# 6502v2.net
KiCad netlist of a schematic drawn in EasyEDA
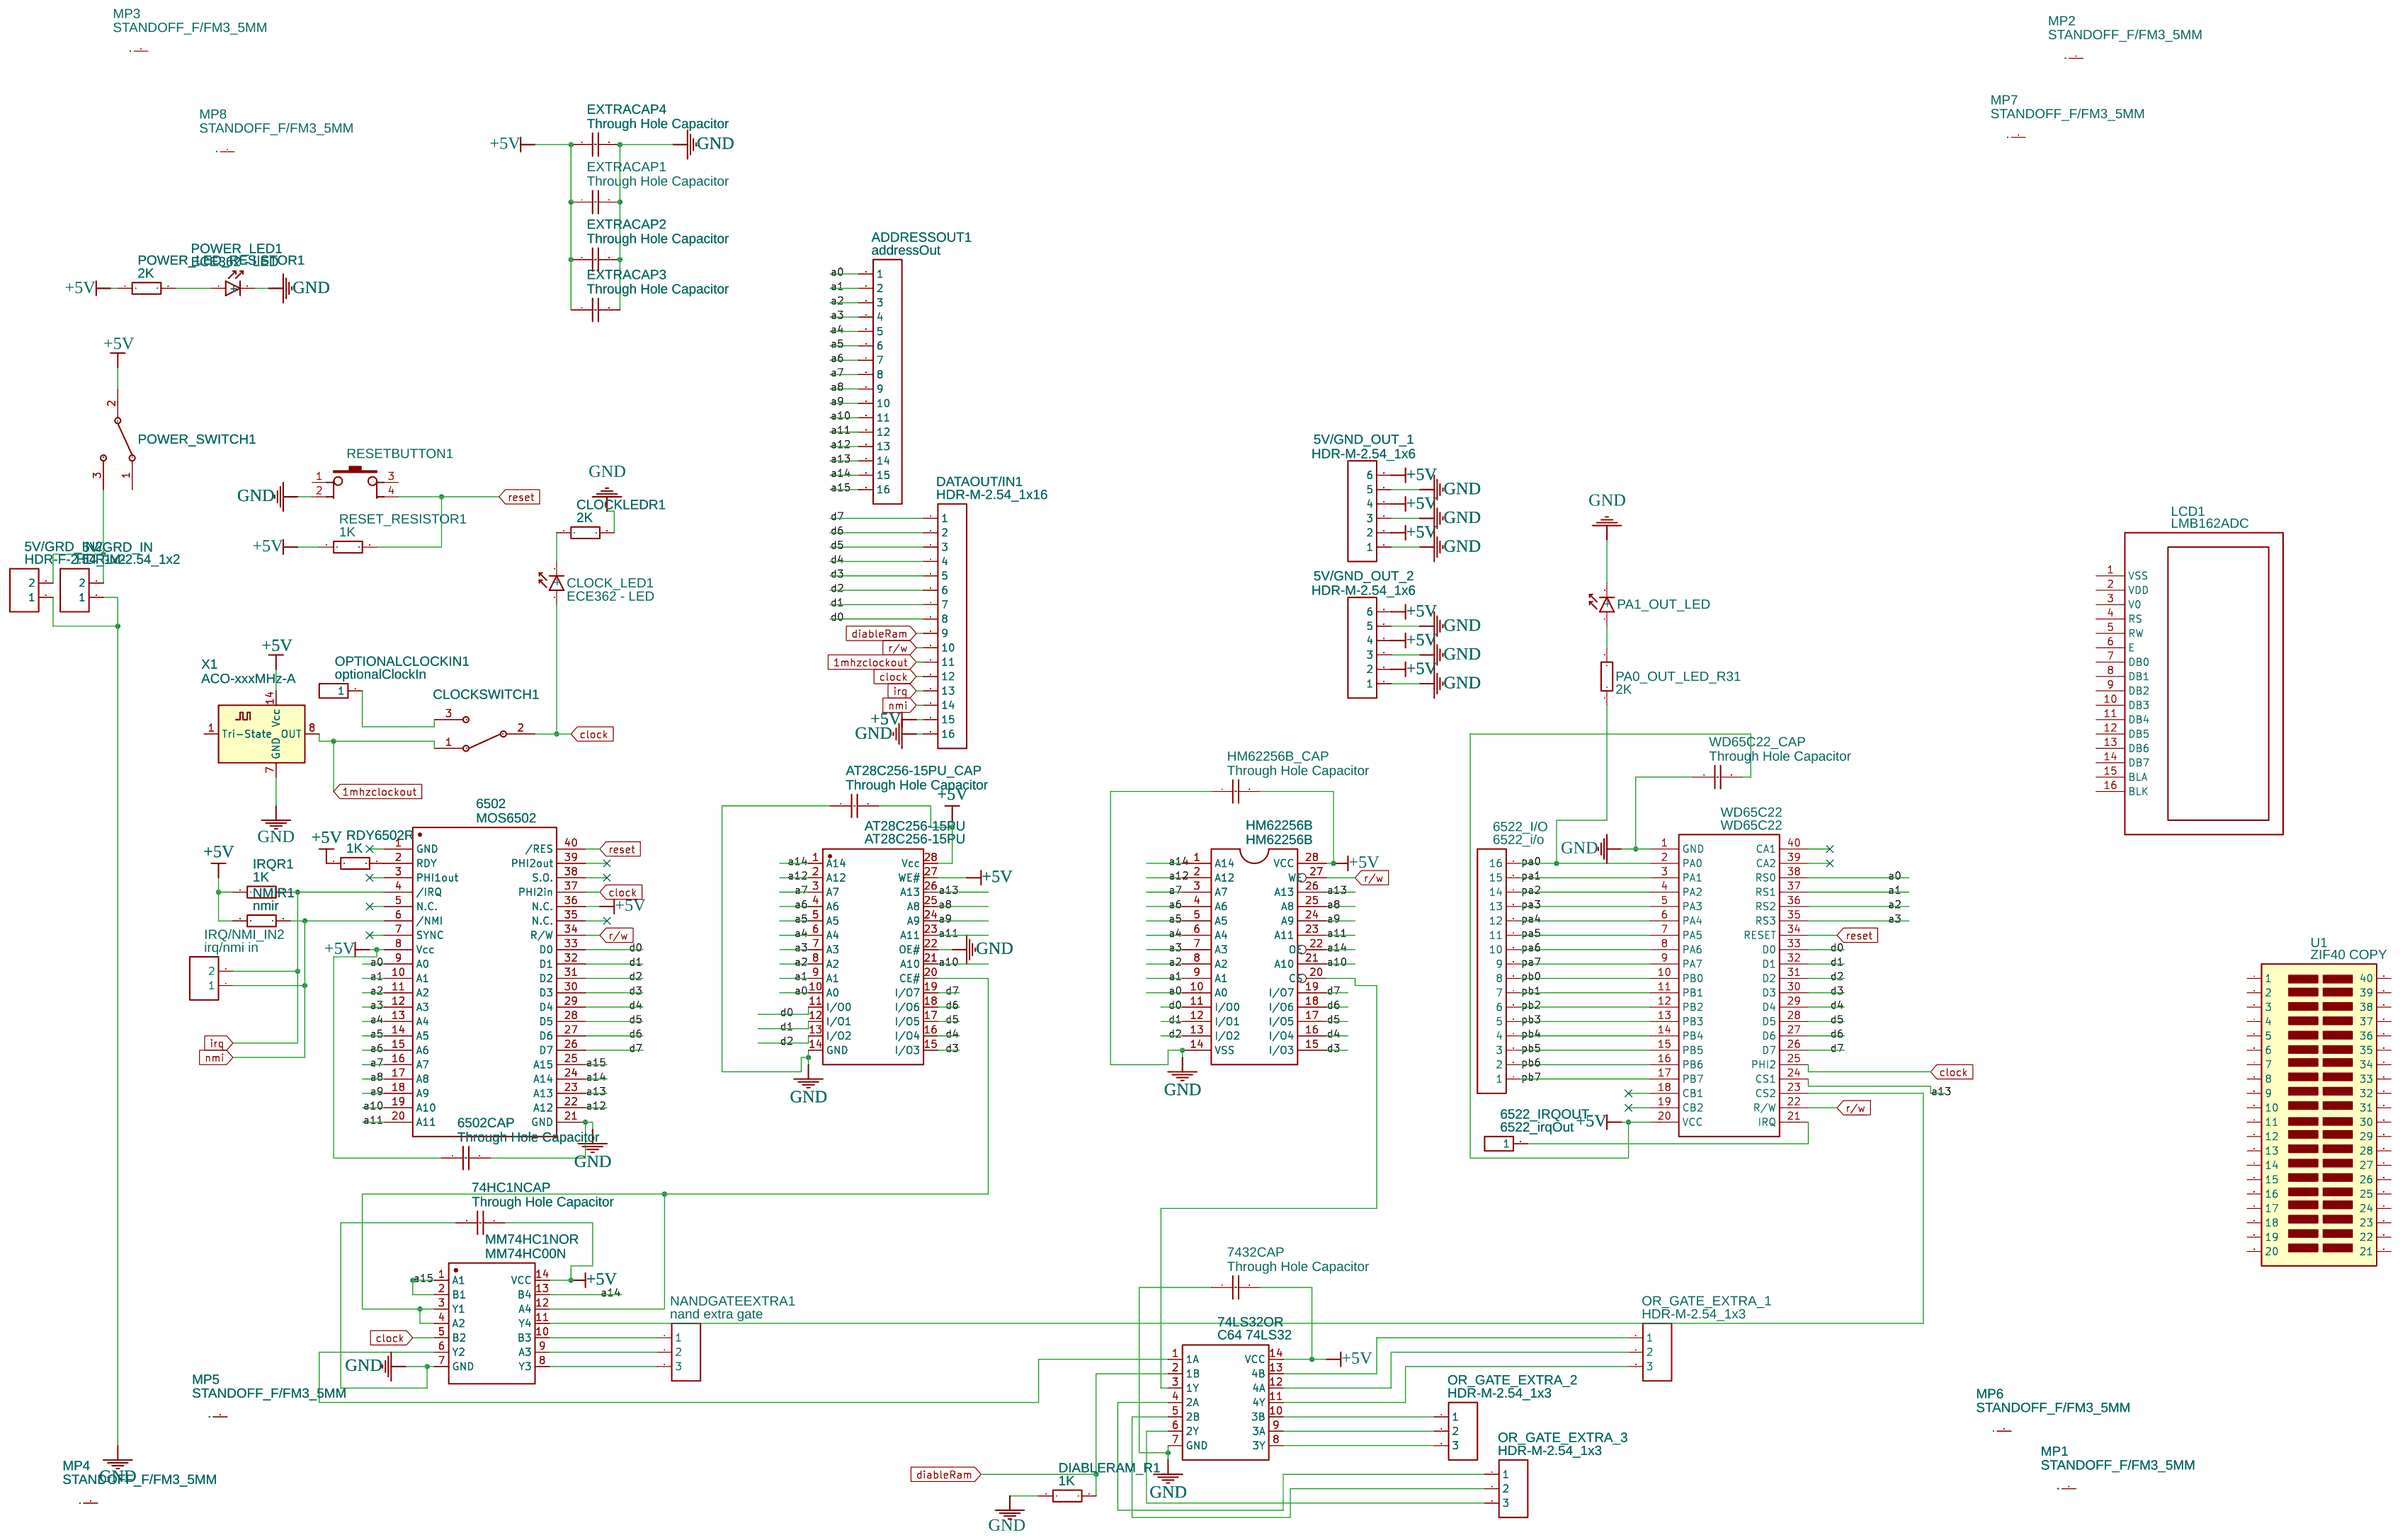
[diagram p0: schematic sheet]

(export (version "E")
  (design (tool "Eeschema 10.0.6"))
  (components
    (comp (ref "5V/GND_OUT_1")
      (value "HDR-M-2.54_1x6")
      (fields (field (name "BOM_Supplier Part") "C190819"))
      (libsource (lib "") (part "HDR-M-2.54_1x6"))
    )
    (comp (ref "5V/GND_OUT_2")
      (value "HDR-M-2.54_1x6")
      (fields (field (name "BOM_Supplier Part") "C190819"))
      (libsource (lib "") (part "HDR-M-2.54_1x6"))
    )
    (comp (ref "5V/GRD_IN")
      (value "HDR-M-2.54_1x2")
      (fields (field (name "BOM_Supplier Part") "C124375"))
      (libsource (lib "") (part "HDR-M-2.54_1x2"))
    )
    (comp (ref "5V/GRD_IN2")
      (value "HDR-F-2.54_1x2")
      (fields (field (name "BOM_Supplier Part") "C49661"))
      (libsource (lib "") (part "HDR-F-2.54_1x2_1"))
    )
    (comp (ref "74HC1NCAP")
      (value "Through Hole Capacitor")
      (fields (field (name "BOM_Manufacturer Part") "TAP106K016SCS"))
      (libsource (lib "") (part "Through Hole Capacitor_2"))
    )
    (comp (ref "74LS32OR") (value "C64 74LS32") (libsource (lib "") (part "C64 74LS32")))
    (comp (ref "6502") (value "MOS6502") (libsource (lib "") (part "MOS6502")))
    (comp (ref "6502CAP")
      (value "Through Hole Capacitor")
      (fields (field (name "BOM_Manufacturer Part") "TAP106K016SCS"))
      (libsource (lib "") (part "Through Hole Capacitor_3"))
    )
    (comp (ref "6522_I/O") (value "6522_i/o") (libsource (lib "") (part "HDR-M-2.54_1x16_1")))
    (comp (ref "6522_IRQOUT")
      (value "6522_irqOut")
      (fields (field (name "BOM_Supplier Part") "C81276"))
      (libsource (lib "") (part "HDR-M-2.54_1x1"))
    )
    (comp (ref "7432CAP")
      (value "Through Hole Capacitor")
      (fields (field (name "BOM_Manufacturer Part") "TAP106K016SCS"))
      (libsource (lib "") (part "Through Hole Capacitor_4"))
    )
    (comp (ref "ADDRESSOUT1") (value "addressOut") (libsource (lib "") (part "HDR-M-2.54_1x16")))
    (comp (ref "AT28C256-15PU")
      (value "AT28C256-15PU")
      (fields (field (name "BOM_Supplier Part") "C1348752"))
      (libsource (lib "") (part "AT28C256-15PU"))
    )
    (comp (ref "AT28C256-15PU_CAP")
      (value "Through Hole Capacitor")
      (fields (field (name "BOM_Manufacturer Part") "TAP106K016SCS"))
      (libsource (lib "") (part "Through Hole Capacitor_5"))
    )
    (comp (ref "CLOCKLEDR1")
      (value "2K")
      (fields
        (field (name "BOM_Manufacturer Part") "EWWR0006J10K0T9")
        (field (name "BOM_Supplier Part") "C348946")
      )
      (libsource (lib "") (part "GENERIC THROUGH HOLE RESISTOR 2_3"))
    )
    (comp (ref "CLOCKSWITCH1")
      (value "Slide Switches_SPDT(Single Pole Double Throw)")
      (libsource (lib "") (part "Slide Switches_SPDT(Single Pole Double Throw)"))
    )
    (comp (ref "CLOCK_LED1") (value "ECE362 - LED") (libsource (lib "") (part "ECE362 - LED")))
    (comp (ref "DATAOUT/IN1") (value "HDR-M-2.54_1x16") (libsource (lib "") (part "HDR-M-2.54_1x16_2")))
    (comp (ref "DIABLERAM_R1")
      (value "1K")
      (fields
        (field (name "BOM_Manufacturer Part") "EWWR0006J10K0T9")
        (field (name "BOM_Supplier Part") "C348946")
      )
      (libsource (lib "") (part "GENERIC THROUGH HOLE RESISTOR 2_1"))
    )
    (comp (ref "EXTRACAP1")
      (value "Through Hole Capacitor")
      (fields (field (name "BOM_Manufacturer Part") "TAP106K016SCS"))
      (libsource (lib "") (part "Through Hole Capacitor_1"))
    )
    (comp (ref "EXTRACAP2")
      (value "Through Hole Capacitor")
      (fields (field (name "BOM_Manufacturer Part") "TAP106K016SCS"))
      (libsource (lib "") (part "Through Hole Capacitor_1"))
    )
    (comp (ref "EXTRACAP3")
      (value "Through Hole Capacitor")
      (fields (field (name "BOM_Manufacturer Part") "TAP106K016SCS"))
      (libsource (lib "") (part "Through Hole Capacitor_1"))
    )
    (comp (ref "EXTRACAP4")
      (value "Through Hole Capacitor")
      (fields (field (name "BOM_Manufacturer Part") "TAP106K016SCS"))
      (libsource (lib "") (part "Through Hole Capacitor_1"))
    )
    (comp (ref "HM62256B") (value "HM62256B") (libsource (lib "") (part "HM62256B")))
    (comp (ref "HM62256B_CAP")
      (value "Through Hole Capacitor")
      (fields (field (name "BOM_Manufacturer Part") "TAP106K016SCS"))
      (libsource (lib "") (part "Through Hole Capacitor"))
    )
    (comp (ref "IRQ/NMI_IN2")
      (value "irq/nmi in")
      (fields (field (name "BOM_Supplier Part") "C49661"))
      (libsource (lib "") (part "HDR-F-2.54_1x2"))
    )
    (comp (ref "IRQR1")
      (value "1K")
      (fields
        (field (name "BOM_Manufacturer Part") "EWWR0006J10K0T9")
        (field (name "BOM_Supplier Part") "C348946")
      )
      (libsource (lib "") (part "GENERIC THROUGH HOLE RESISTOR 2"))
    )
    (comp (ref "LCD1")
      (value "LMB162ADC")
      (fields (field (name "Manufacturer") "TOPWAY"))
      (libsource (lib "") (part "LMB162ADC"))
    )
    (comp (ref "MM74HC1NOR") (value "MM74HC00N") (libsource (lib "") (part "MM74HC00N")))
    (comp (ref "MP1") (value "STANDOFF_F/FM3_5MM") (libsource (lib "") (part "STANDOFF_F/FM3_5MM")))
    (comp (ref "MP2") (value "STANDOFF_F/FM3_5MM") (libsource (lib "") (part "STANDOFF_F/FM3_5MM")))
    (comp (ref "MP3") (value "STANDOFF_F/FM3_5MM") (libsource (lib "") (part "STANDOFF_F/FM3_5MM")))
    (comp (ref "MP4") (value "STANDOFF_F/FM3_5MM") (libsource (lib "") (part "STANDOFF_F/FM3_5MM")))
    (comp (ref "MP5") (value "STANDOFF_F/FM3_5MM") (libsource (lib "") (part "STANDOFF_F/FM3_5MM")))
    (comp (ref "MP6") (value "STANDOFF_F/FM3_5MM") (libsource (lib "") (part "STANDOFF_F/FM3_5MM")))
    (comp (ref "MP7") (value "STANDOFF_F/FM3_5MM") (libsource (lib "") (part "STANDOFF_F/FM3_5MM")))
    (comp (ref "MP8") (value "STANDOFF_F/FM3_5MM") (libsource (lib "") (part "STANDOFF_F/FM3_5MM")))
    (comp (ref "NANDGATEEXTRA1")
      (value "nand extra gate")
      (fields (field (name "BOM_Supplier Part") "C180248"))
      (libsource (lib "") (part "HDR-M-2.54_1x3_1"))
    )
    (comp (ref "NMIR1")
      (value "nmir")
      (fields
        (field (name "BOM_Manufacturer Part") "EWWR0006J10K0T9")
        (field (name "BOM_Supplier Part") "C348946")
      )
      (libsource (lib "") (part "GENERIC THROUGH HOLE RESISTOR 2_4"))
    )
    (comp (ref "OPTIONALCLOCKIN1")
      (value "optionalClockIn")
      (fields (field (name "BOM_Supplier Part") "C81276"))
      (libsource (lib "") (part "HDR-M-2.54_1x1_1"))
    )
    (comp (ref "OR_GATE_EXTRA_1")
      (value "HDR-M-2.54_1x3")
      (fields (field (name "BOM_Supplier Part") "C180248"))
      (libsource (lib "") (part "HDR-M-2.54_1x3"))
    )
    (comp (ref "OR_GATE_EXTRA_2")
      (value "HDR-M-2.54_1x3")
      (fields (field (name "BOM_Supplier Part") "C180248"))
      (libsource (lib "") (part "HDR-M-2.54_1x3"))
    )
    (comp (ref "OR_GATE_EXTRA_3")
      (value "HDR-M-2.54_1x3")
      (fields (field (name "BOM_Supplier Part") "C180248"))
      (libsource (lib "") (part "HDR-M-2.54_1x3"))
    )
    (comp (ref "PA0_OUT_LED_R31")
      (value "2K")
      (fields
        (field (name "BOM_Manufacturer Part") "EWWR0006J10K0T9")
        (field (name "BOM_Supplier Part") "C348946")
      )
      (libsource (lib "") (part "GENERIC THROUGH HOLE RESISTOR 2_5"))
    )
    (comp (ref "PA1_OUT_LED") (value "ECE362 - LED") (libsource (lib "") (part "ECE362 - LED_2")))
    (comp (ref "POWER_LED1") (value "ECE362 - LED") (libsource (lib "") (part "ECE362 - LED_1")))
    (comp (ref "POWER_LED_RESISTOR1")
      (value "2K")
      (fields
        (field (name "BOM_Manufacturer Part") "EWWR0006J10K0T9")
        (field (name "BOM_Supplier Part") "C348946")
      )
      (libsource (lib "") (part "GENERIC THROUGH HOLE RESISTOR 2_7"))
    )
    (comp (ref "POWER_SWITCH1")
      (value "Slide Switches_SPDT(Single Pole Double Throw)")
      (libsource (lib "") (part "Slide Switches_SPDT(Single Pole Double Throw)_1"))
    )
    (comp (ref "RDY6502R")
      (value "1K")
      (fields
        (field (name "BOM_Manufacturer Part") "EWWR0006J10K0T9")
        (field (name "BOM_Supplier Part") "C348946")
      )
      (libsource (lib "") (part "GENERIC THROUGH HOLE RESISTOR 2_6"))
    )
    (comp (ref "RESETBUTTON1")
      (value "PUSHBUTTON 4PIN (4.5MM*6.1MM) COPY")
      (libsource (lib "") (part "PUSHBUTTON 4PIN (4.5MM*6.1MM) COPY"))
    )
    (comp (ref "RESET_RESISTOR1")
      (value "1K")
      (fields
        (field (name "BOM_Manufacturer Part") "EWWR0006J10K0T9")
        (field (name "BOM_Supplier Part") "C348946")
      )
      (libsource (lib "") (part "GENERIC THROUGH HOLE RESISTOR 2_2"))
    )
    (comp (ref "U1")
      (value "ZIF40 COPY")
      (fields (field (name "BOM_Manufacturer Part") "New SchematicLib"))
      (libsource (lib "") (part "ZIF40 COPY"))
    )
    (comp (ref "WD65C22") (value "WD65C22") (libsource (lib "") (part "WD65C22")))
    (comp (ref "WD65C22_CAP")
      (value "Through Hole Capacitor")
      (fields (field (name "BOM_Manufacturer Part") "TAP106K016SCS"))
      (libsource (lib "") (part "Through Hole Capacitor_6"))
    )
    (comp (ref "X1") (value "ACO-xxxMHz-A") (libsource (lib "") (part "ACO-xxxMHz-A")))
  )
  (nets
    (net (code "1") (name "+5V") (class "Default")
      (node (ref "5V/GND_OUT_1") (pin "2") (pinfunction "2_2") (pintype "input"))
      (node (ref "5V/GND_OUT_1") (pin "4") (pinfunction "4_4") (pintype "input"))
      (node (ref "5V/GND_OUT_1") (pin "6") (pinfunction "6_6") (pintype "input"))
      (node (ref "5V/GND_OUT_2") (pin "2") (pinfunction "2_2") (pintype "input"))
      (node (ref "5V/GND_OUT_2") (pin "4") (pinfunction "4_4") (pintype "input"))
      (node (ref "5V/GND_OUT_2") (pin "6") (pinfunction "6_6") (pintype "input"))
      (node (ref "6502") (pin "36") (pinfunction "N.C._36") (pintype "unspecified"))
      (node (ref "6502") (pin "8") (pinfunction "Vcc_8") (pintype "unspecified"))
      (node (ref "6502CAP") (pin "1") (pinfunction "1_1") (pintype "unspecified"))
      (node (ref "7432CAP") (pin "2") (pinfunction "2_2") (pintype "unspecified"))
      (node (ref "74HC1NCAP") (pin "2") (pinfunction "2_2") (pintype "unspecified"))
      (node (ref "74LS32OR") (pin "14") (pinfunction "VCC_14") (pintype "unspecified"))
      (node (ref "AT28C256-15PU") (pin "27") (pinfunction "WE#_27") (pintype "unspecified"))
      (node (ref "AT28C256-15PU") (pin "28") (pinfunction "Vcc_28") (pintype "unspecified"))
      (node (ref "AT28C256-15PU_CAP") (pin "2") (pinfunction "2_2") (pintype "unspecified"))
      (node (ref "DATAOUT/IN1") (pin "15") (pinfunction "15_15") (pintype "unspecified"))
      (node (ref "EXTRACAP1") (pin "1") (pinfunction "1_1") (pintype "unspecified"))
      (node (ref "EXTRACAP2") (pin "1") (pinfunction "1_1") (pintype "unspecified"))
      (node (ref "EXTRACAP3") (pin "1") (pinfunction "1_1") (pintype "unspecified"))
      (node (ref "EXTRACAP4") (pin "1") (pinfunction "1_1") (pintype "unspecified"))
      (node (ref "HM62256B") (pin "28") (pinfunction "VCC_28") (pintype "unspecified"))
      (node (ref "HM62256B_CAP") (pin "2") (pinfunction "2_2") (pintype "unspecified"))
      (node (ref "IRQR1") (pin "1") (pinfunction "1_1") (pintype "unspecified"))
      (node (ref "MM74HC1NOR") (pin "14") (pinfunction "VCC_14") (pintype "unspecified"))
      (node (ref "NMIR1") (pin "1") (pinfunction "1_1") (pintype "unspecified"))
      (node (ref "POWER_LED_RESISTOR1") (pin "1") (pinfunction "1_1") (pintype "unspecified"))
      (node (ref "POWER_SWITCH1") (pin "2") (pinfunction "2_2") (pintype "unspecified"))
      (node (ref "RDY6502R") (pin "1") (pinfunction "1_1") (pintype "unspecified"))
      (node (ref "RESET_RESISTOR1") (pin "1") (pinfunction "1_1") (pintype "unspecified"))
      (node (ref "WD65C22") (pin "20") (pinfunction "VCC_20") (pintype "unspecified"))
      (node (ref "WD65C22_CAP") (pin "2") (pinfunction "2_2") (pintype "unspecified"))
      (node (ref "X1") (pin "14") (pinfunction "Vcc_14") (pintype "bidirectional"))
    )
    (net (code "2") (name "/a0") (class "Default")
      (node (ref "6502") (pin "9") (pinfunction "A0_9") (pintype "unspecified"))
      (node (ref "ADDRESSOUT1") (pin "1") (pinfunction "1_1") (pintype "unspecified"))
      (node (ref "AT28C256-15PU") (pin "10") (pinfunction "A0_10") (pintype "unspecified"))
      (node (ref "HM62256B") (pin "10") (pinfunction "A0_10") (pintype "unspecified"))
      (node (ref "WD65C22") (pin "38") (pinfunction "RS0_38") (pintype "unspecified"))
    )
    (net (code "3") (name "/a1") (class "Default")
      (node (ref "6502") (pin "10") (pinfunction "A1_10") (pintype "unspecified"))
      (node (ref "ADDRESSOUT1") (pin "2") (pinfunction "2_2") (pintype "unspecified"))
      (node (ref "AT28C256-15PU") (pin "9") (pinfunction "A1_9") (pintype "unspecified"))
      (node (ref "HM62256B") (pin "9") (pinfunction "A1_9") (pintype "unspecified"))
      (node (ref "WD65C22") (pin "37") (pinfunction "RS1_37") (pintype "unspecified"))
    )
    (net (code "4") (name "/a2") (class "Default")
      (node (ref "6502") (pin "11") (pinfunction "A2_11") (pintype "unspecified"))
      (node (ref "ADDRESSOUT1") (pin "3") (pinfunction "3_3") (pintype "unspecified"))
      (node (ref "AT28C256-15PU") (pin "8") (pinfunction "A2_8") (pintype "unspecified"))
      (node (ref "HM62256B") (pin "8") (pinfunction "A2_8") (pintype "unspecified"))
      (node (ref "WD65C22") (pin "36") (pinfunction "RS2_36") (pintype "unspecified"))
    )
    (net (code "5") (name "/a3") (class "Default")
      (node (ref "6502") (pin "12") (pinfunction "A3_12") (pintype "unspecified"))
      (node (ref "ADDRESSOUT1") (pin "4") (pinfunction "4_4") (pintype "unspecified"))
      (node (ref "AT28C256-15PU") (pin "7") (pinfunction "A3_7") (pintype "unspecified"))
      (node (ref "HM62256B") (pin "7") (pinfunction "A3_7") (pintype "unspecified"))
      (node (ref "WD65C22") (pin "35") (pinfunction "RS3_35") (pintype "unspecified"))
    )
    (net (code "6") (name "/a4") (class "Default")
      (node (ref "6502") (pin "13") (pinfunction "A4_13") (pintype "unspecified"))
      (node (ref "ADDRESSOUT1") (pin "5") (pinfunction "5_5") (pintype "unspecified"))
      (node (ref "AT28C256-15PU") (pin "6") (pinfunction "A4_6") (pintype "unspecified"))
      (node (ref "HM62256B") (pin "6") (pinfunction "A4_6") (pintype "unspecified"))
    )
    (net (code "7") (name "/a5") (class "Default")
      (node (ref "6502") (pin "14") (pinfunction "A5_14") (pintype "unspecified"))
      (node (ref "ADDRESSOUT1") (pin "6") (pinfunction "6_6") (pintype "unspecified"))
      (node (ref "AT28C256-15PU") (pin "5") (pinfunction "A5_5") (pintype "unspecified"))
      (node (ref "HM62256B") (pin "5") (pinfunction "A5_5") (pintype "unspecified"))
    )
    (net (code "8") (name "/a6") (class "Default")
      (node (ref "6502") (pin "15") (pinfunction "A6_15") (pintype "unspecified"))
      (node (ref "ADDRESSOUT1") (pin "7") (pinfunction "7_7") (pintype "unspecified"))
      (node (ref "AT28C256-15PU") (pin "4") (pinfunction "A6_4") (pintype "unspecified"))
      (node (ref "HM62256B") (pin "4") (pinfunction "A6_4") (pintype "unspecified"))
    )
    (net (code "9") (name "/a7") (class "Default")
      (node (ref "6502") (pin "16") (pinfunction "A7_16") (pintype "unspecified"))
      (node (ref "ADDRESSOUT1") (pin "8") (pinfunction "8_8") (pintype "unspecified"))
      (node (ref "AT28C256-15PU") (pin "3") (pinfunction "A7_3") (pintype "unspecified"))
      (node (ref "HM62256B") (pin "3") (pinfunction "A7_3") (pintype "unspecified"))
    )
    (net (code "10") (name "/a8") (class "Default")
      (node (ref "6502") (pin "17") (pinfunction "A8_17") (pintype "unspecified"))
      (node (ref "ADDRESSOUT1") (pin "9") (pinfunction "9_9") (pintype "unspecified"))
      (node (ref "AT28C256-15PU") (pin "25") (pinfunction "A8_25") (pintype "unspecified"))
      (node (ref "HM62256B") (pin "25") (pinfunction "A8_25") (pintype "unspecified"))
    )
    (net (code "11") (name "/a9") (class "Default")
      (node (ref "6502") (pin "18") (pinfunction "A9_18") (pintype "unspecified"))
      (node (ref "ADDRESSOUT1") (pin "10") (pinfunction "10_10") (pintype "unspecified"))
      (node (ref "AT28C256-15PU") (pin "24") (pinfunction "A9_24") (pintype "unspecified"))
      (node (ref "HM62256B") (pin "24") (pinfunction "A9_24") (pintype "unspecified"))
    )
    (net (code "12") (name "/a10") (class "Default")
      (node (ref "6502") (pin "19") (pinfunction "A10_19") (pintype "unspecified"))
      (node (ref "ADDRESSOUT1") (pin "11") (pinfunction "11_11") (pintype "unspecified"))
      (node (ref "AT28C256-15PU") (pin "21") (pinfunction "A10_21") (pintype "unspecified"))
      (node (ref "HM62256B") (pin "21") (pinfunction "A10_21") (pintype "unspecified"))
    )
    (net (code "13") (name "/a11") (class "Default")
      (node (ref "6502") (pin "20") (pinfunction "A11_20") (pintype "unspecified"))
      (node (ref "ADDRESSOUT1") (pin "12") (pinfunction "12_12") (pintype "unspecified"))
      (node (ref "AT28C256-15PU") (pin "23") (pinfunction "A11_23") (pintype "unspecified"))
      (node (ref "HM62256B") (pin "23") (pinfunction "A11_23") (pintype "unspecified"))
    )
    (net (code "14") (name "/a12") (class "Default")
      (node (ref "6502") (pin "22") (pinfunction "A12_22") (pintype "unspecified"))
      (node (ref "ADDRESSOUT1") (pin "13") (pinfunction "13_13") (pintype "unspecified"))
      (node (ref "AT28C256-15PU") (pin "2") (pinfunction "A12_2") (pintype "unspecified"))
      (node (ref "HM62256B") (pin "2") (pinfunction "A12_2") (pintype "unspecified"))
    )
    (net (code "15") (name "/a13") (class "Default")
      (node (ref "6502") (pin "23") (pinfunction "A13_23") (pintype "unspecified"))
      (node (ref "ADDRESSOUT1") (pin "14") (pinfunction "14_14") (pintype "unspecified"))
      (node (ref "AT28C256-15PU") (pin "26") (pinfunction "A13_26") (pintype "unspecified"))
      (node (ref "HM62256B") (pin "26") (pinfunction "A13_26") (pintype "unspecified"))
      (node (ref "WD65C22") (pin "24") (pinfunction "CS1_24") (pintype "unspecified"))
    )
    (net (code "16") (name "/a14") (class "Default")
      (node (ref "6502") (pin "24") (pinfunction "A14_24") (pintype "unspecified"))
      (node (ref "ADDRESSOUT1") (pin "15") (pinfunction "15_15") (pintype "unspecified"))
      (node (ref "AT28C256-15PU") (pin "1") (pinfunction "A14_1") (pintype "unspecified"))
      (node (ref "HM62256B") (pin "1") (pinfunction "A14_1") (pintype "unspecified"))
      (node (ref "HM62256B") (pin "22") (pinfunction "OE_22") (pintype "unspecified"))
      (node (ref "MM74HC1NOR") (pin "13") (pinfunction "B4_13") (pintype "unspecified"))
    )
    (net (code "17") (name "/a15") (class "Default")
      (node (ref "6502") (pin "25") (pinfunction "A15_25") (pintype "unspecified"))
      (node (ref "ADDRESSOUT1") (pin "16") (pinfunction "16_16") (pintype "unspecified"))
      (node (ref "MM74HC1NOR") (pin "1") (pinfunction "A1_1") (pintype "unspecified"))
      (node (ref "MM74HC1NOR") (pin "2") (pinfunction "B1_2") (pintype "unspecified"))
    )
    (net (code "18") (name "/d0") (class "Default")
      (node (ref "6502") (pin "33") (pinfunction "D0_33") (pintype "unspecified"))
      (node (ref "AT28C256-15PU") (pin "11") (pinfunction "I/O0_11") (pintype "unspecified"))
      (node (ref "DATAOUT/IN1") (pin "8") (pinfunction "8_8") (pintype "unspecified"))
      (node (ref "HM62256B") (pin "11") (pinfunction "I/O0_11") (pintype "unspecified"))
      (node (ref "WD65C22") (pin "33") (pinfunction "D0_33") (pintype "unspecified"))
    )
    (net (code "19") (name "/d1") (class "Default")
      (node (ref "6502") (pin "32") (pinfunction "D1_32") (pintype "unspecified"))
      (node (ref "AT28C256-15PU") (pin "12") (pinfunction "I/O1_12") (pintype "unspecified"))
      (node (ref "DATAOUT/IN1") (pin "7") (pinfunction "7_7") (pintype "unspecified"))
      (node (ref "HM62256B") (pin "12") (pinfunction "I/O1_12") (pintype "unspecified"))
      (node (ref "WD65C22") (pin "32") (pinfunction "D1_32") (pintype "unspecified"))
    )
    (net (code "20") (name "/d2") (class "Default")
      (node (ref "6502") (pin "31") (pinfunction "D2_31") (pintype "unspecified"))
      (node (ref "AT28C256-15PU") (pin "13") (pinfunction "I/O2_13") (pintype "unspecified"))
      (node (ref "DATAOUT/IN1") (pin "6") (pinfunction "6_6") (pintype "unspecified"))
      (node (ref "HM62256B") (pin "13") (pinfunction "I/O2_13") (pintype "unspecified"))
      (node (ref "WD65C22") (pin "31") (pinfunction "D2_31") (pintype "unspecified"))
    )
    (net (code "21") (name "/d3") (class "Default")
      (node (ref "6502") (pin "30") (pinfunction "D3_30") (pintype "unspecified"))
      (node (ref "AT28C256-15PU") (pin "15") (pinfunction "I/O3_15") (pintype "unspecified"))
      (node (ref "DATAOUT/IN1") (pin "5") (pinfunction "5_5") (pintype "unspecified"))
      (node (ref "HM62256B") (pin "15") (pinfunction "I/O3_15") (pintype "unspecified"))
      (node (ref "WD65C22") (pin "30") (pinfunction "D3_30") (pintype "unspecified"))
    )
    (net (code "22") (name "/d4") (class "Default")
      (node (ref "6502") (pin "29") (pinfunction "D4_29") (pintype "unspecified"))
      (node (ref "AT28C256-15PU") (pin "16") (pinfunction "I/O4_16") (pintype "unspecified"))
      (node (ref "DATAOUT/IN1") (pin "4") (pinfunction "4_4") (pintype "unspecified"))
      (node (ref "HM62256B") (pin "16") (pinfunction "I/O4_16") (pintype "unspecified"))
      (node (ref "WD65C22") (pin "29") (pinfunction "D4_29") (pintype "unspecified"))
    )
    (net (code "23") (name "/d5") (class "Default")
      (node (ref "6502") (pin "28") (pinfunction "D5_28") (pintype "unspecified"))
      (node (ref "AT28C256-15PU") (pin "17") (pinfunction "I/O5_17") (pintype "unspecified"))
      (node (ref "DATAOUT/IN1") (pin "3") (pinfunction "3_3") (pintype "unspecified"))
      (node (ref "HM62256B") (pin "17") (pinfunction "I/O5_17") (pintype "unspecified"))
      (node (ref "WD65C22") (pin "28") (pinfunction "D5_28") (pintype "unspecified"))
    )
    (net (code "24") (name "/d6") (class "Default")
      (node (ref "6502") (pin "27") (pinfunction "D6_27") (pintype "unspecified"))
      (node (ref "AT28C256-15PU") (pin "18") (pinfunction "I/O6_18") (pintype "unspecified"))
      (node (ref "DATAOUT/IN1") (pin "2") (pinfunction "2_2") (pintype "unspecified"))
      (node (ref "HM62256B") (pin "18") (pinfunction "I/O6_18") (pintype "unspecified"))
      (node (ref "WD65C22") (pin "27") (pinfunction "D6_27") (pintype "unspecified"))
    )
    (net (code "25") (name "/d7") (class "Default")
      (node (ref "6502") (pin "26") (pinfunction "D7_26") (pintype "unspecified"))
      (node (ref "AT28C256-15PU") (pin "19") (pinfunction "I/O7_19") (pintype "unspecified"))
      (node (ref "DATAOUT/IN1") (pin "1") (pinfunction "1_1") (pintype "unspecified"))
      (node (ref "HM62256B") (pin "19") (pinfunction "I/O7_19") (pintype "unspecified"))
      (node (ref "WD65C22") (pin "26") (pinfunction "D7_26") (pintype "unspecified"))
    )
    (net (code "26") (name "/pa0") (class "Default")
      (node (ref "6522_I/O") (pin "16") (pinfunction "16_16") (pintype "unspecified"))
      (node (ref "PA0_OUT_LED_R31") (pin "1") (pinfunction "1_1") (pintype "unspecified"))
      (node (ref "WD65C22") (pin "2") (pinfunction "PA0_2") (pintype "unspecified"))
    )
    (net (code "27") (name "/pa1") (class "Default")
      (node (ref "6522_I/O") (pin "15") (pinfunction "15_15") (pintype "unspecified"))
      (node (ref "WD65C22") (pin "3") (pinfunction "PA1_3") (pintype "unspecified"))
    )
    (net (code "28") (name "/pa2") (class "Default")
      (node (ref "6522_I/O") (pin "14") (pinfunction "14_14") (pintype "unspecified"))
      (node (ref "WD65C22") (pin "4") (pinfunction "PA2_4") (pintype "unspecified"))
    )
    (net (code "29") (name "/pa3") (class "Default")
      (node (ref "6522_I/O") (pin "13") (pinfunction "13_13") (pintype "unspecified"))
      (node (ref "WD65C22") (pin "5") (pinfunction "PA3_5") (pintype "unspecified"))
    )
    (net (code "30") (name "/pa4") (class "Default")
      (node (ref "6522_I/O") (pin "12") (pinfunction "12_12") (pintype "unspecified"))
      (node (ref "WD65C22") (pin "6") (pinfunction "PA4_6") (pintype "unspecified"))
    )
    (net (code "31") (name "/pa5") (class "Default")
      (node (ref "6522_I/O") (pin "11") (pinfunction "11_11") (pintype "unspecified"))
      (node (ref "WD65C22") (pin "7") (pinfunction "PA5_7") (pintype "unspecified"))
    )
    (net (code "32") (name "/pa6") (class "Default")
      (node (ref "6522_I/O") (pin "10") (pinfunction "10_10") (pintype "unspecified"))
      (node (ref "WD65C22") (pin "8") (pinfunction "PA6_8") (pintype "unspecified"))
    )
    (net (code "33") (name "/pa7") (class "Default")
      (node (ref "6522_I/O") (pin "9") (pinfunction "9_9") (pintype "unspecified"))
      (node (ref "WD65C22") (pin "9") (pinfunction "PA7_9") (pintype "unspecified"))
    )
    (net (code "34") (name "/pb0") (class "Default")
      (node (ref "6522_I/O") (pin "8") (pinfunction "8_8") (pintype "unspecified"))
      (node (ref "WD65C22") (pin "10") (pinfunction "PB0_10") (pintype "unspecified"))
    )
    (net (code "35") (name "/pb1") (class "Default")
      (node (ref "6522_I/O") (pin "7") (pinfunction "7_7") (pintype "unspecified"))
      (node (ref "WD65C22") (pin "11") (pinfunction "PB1_11") (pintype "unspecified"))
    )
    (net (code "36") (name "/pb2") (class "Default")
      (node (ref "6522_I/O") (pin "6") (pinfunction "6_6") (pintype "unspecified"))
      (node (ref "WD65C22") (pin "12") (pinfunction "PB2_12") (pintype "unspecified"))
    )
    (net (code "37") (name "/pb3") (class "Default")
      (node (ref "6522_I/O") (pin "5") (pinfunction "5_5") (pintype "unspecified"))
      (node (ref "WD65C22") (pin "13") (pinfunction "PB3_13") (pintype "unspecified"))
    )
    (net (code "38") (name "/pb4") (class "Default")
      (node (ref "6522_I/O") (pin "4") (pinfunction "4_4") (pintype "unspecified"))
      (node (ref "WD65C22") (pin "14") (pinfunction "PB4_14") (pintype "unspecified"))
    )
    (net (code "39") (name "/pb5") (class "Default")
      (node (ref "6522_I/O") (pin "3") (pinfunction "3_3") (pintype "unspecified"))
      (node (ref "WD65C22") (pin "15") (pinfunction "PB5_15") (pintype "unspecified"))
    )
    (net (code "40") (name "/pb6") (class "Default")
      (node (ref "6522_I/O") (pin "2") (pinfunction "2_2") (pintype "unspecified"))
      (node (ref "WD65C22") (pin "16") (pinfunction "PB6_16") (pintype "unspecified"))
    )
    (net (code "41") (name "/pb7") (class "Default")
      (node (ref "6522_I/O") (pin "1") (pinfunction "1_1") (pintype "unspecified"))
      (node (ref "WD65C22") (pin "17") (pinfunction "PB7_17") (pintype "unspecified"))
    )
    (net (code "42") (name "1mhzclockout") (class "Default")
      (node (ref "CLOCKSWITCH1") (pin "1") (pinfunction "1_1") (pintype "unspecified"))
      (node (ref "DATAOUT/IN1") (pin "11") (pinfunction "11_11") (pintype "unspecified"))
      (node (ref "X1") (pin "8") (pinfunction "OUT_8") (pintype "output"))
    )
    (net (code "43") (name "GND") (class "Default")
      (node (ref "5V/GND_OUT_1") (pin "1") (pinfunction "1_1") (pintype "input"))
      (node (ref "5V/GND_OUT_1") (pin "3") (pinfunction "3_3") (pintype "input"))
      (node (ref "5V/GND_OUT_1") (pin "5") (pinfunction "5_5") (pintype "input"))
      (node (ref "5V/GND_OUT_2") (pin "1") (pinfunction "1_1") (pintype "input"))
      (node (ref "5V/GND_OUT_2") (pin "3") (pinfunction "3_3") (pintype "input"))
      (node (ref "5V/GND_OUT_2") (pin "5") (pinfunction "5_5") (pintype "input"))
      (node (ref "5V/GRD_IN") (pin "1") (pinfunction "1_1") (pintype "unspecified"))
      (node (ref "5V/GRD_IN2") (pin "1") (pinfunction "1_1") (pintype "input"))
      (node (ref "6502") (pin "21") (pinfunction "GND_21") (pintype "unspecified"))
      (node (ref "6502CAP") (pin "2") (pinfunction "2_2") (pintype "unspecified"))
      (node (ref "7432CAP") (pin "1") (pinfunction "1_1") (pintype "unspecified"))
      (node (ref "74HC1NCAP") (pin "1") (pinfunction "1_1") (pintype "unspecified"))
      (node (ref "74LS32OR") (pin "7") (pinfunction "GND_7") (pintype "unspecified"))
      (node (ref "AT28C256-15PU") (pin "14") (pinfunction "GND_14") (pintype "unspecified"))
      (node (ref "AT28C256-15PU") (pin "22") (pinfunction "OE#_22") (pintype "unspecified"))
      (node (ref "AT28C256-15PU_CAP") (pin "1") (pinfunction "1_1") (pintype "unspecified"))
      (node (ref "CLOCKLEDR1") (pin "2") (pinfunction "2_2") (pintype "unspecified"))
      (node (ref "DATAOUT/IN1") (pin "16") (pinfunction "16_16") (pintype "unspecified"))
      (node (ref "DIABLERAM_R1") (pin "1") (pinfunction "1_1") (pintype "unspecified"))
      (node (ref "EXTRACAP1") (pin "2") (pinfunction "2_2") (pintype "unspecified"))
      (node (ref "EXTRACAP2") (pin "2") (pinfunction "2_2") (pintype "unspecified"))
      (node (ref "EXTRACAP3") (pin "2") (pinfunction "2_2") (pintype "unspecified"))
      (node (ref "EXTRACAP4") (pin "2") (pinfunction "2_2") (pintype "unspecified"))
      (node (ref "HM62256B") (pin "14") (pinfunction "VSS_14") (pintype "unspecified"))
      (node (ref "HM62256B_CAP") (pin "1") (pinfunction "1_1") (pintype "unspecified"))
      (node (ref "MM74HC1NOR") (pin "7") (pinfunction "GND_7") (pintype "unspecified"))
      (node (ref "PA1_OUT_LED") (pin "2") (pinfunction "-_2") (pintype "unspecified"))
      (node (ref "POWER_LED1") (pin "2") (pinfunction "-_2") (pintype "unspecified"))
      (node (ref "RESETBUTTON1") (pin "2") (pinfunction "2_2") (pintype "input"))
      (node (ref "WD65C22") (pin "1") (pinfunction "GND_1") (pintype "unspecified"))
      (node (ref "WD65C22_CAP") (pin "1") (pinfunction "1_1") (pintype "unspecified"))
      (node (ref "X1") (pin "7") (pinfunction "GND_7") (pintype "bidirectional"))
    )
    (net (code "44") (name "Net-(5V/GRD_IN-Pad2)") (class "Default")
      (node (ref "5V/GRD_IN") (pin "2") (pinfunction "2_2") (pintype "unspecified"))
      (node (ref "5V/GRD_IN2") (pin "2") (pinfunction "2_2") (pintype "input"))
      (node (ref "POWER_SWITCH1") (pin "3") (pinfunction "3_3") (pintype "unspecified"))
    )
    (net (code "45") (name "Net-(74LS32OR-1A)") (class "Default")
      (node (ref "74LS32OR") (pin "1") (pinfunction "1A_1") (pintype "unspecified"))
      (node (ref "MM74HC1NOR") (pin "6") (pinfunction "Y2_6") (pintype "unspecified"))
    )
    (net (code "46") (name "Net-(74LS32OR-1Y)") (class "Default")
      (node (ref "74LS32OR") (pin "3") (pinfunction "1Y_3") (pintype "unspecified"))
      (node (ref "HM62256B") (pin "20") (pinfunction "CS_20") (pintype "unspecified"))
    )
    (net (code "47") (name "Net-(74LS32OR-2A)") (class "Default")
      (node (ref "74LS32OR") (pin "4") (pinfunction "2A_4") (pintype "unspecified"))
      (node (ref "OR_GATE_EXTRA_3") (pin "1") (pinfunction "1_1") (pintype "input"))
    )
    (net (code "48") (name "Net-(74LS32OR-2B)") (class "Default")
      (node (ref "74LS32OR") (pin "5") (pinfunction "2B_5") (pintype "unspecified"))
      (node (ref "OR_GATE_EXTRA_3") (pin "2") (pinfunction "2_2") (pintype "input"))
    )
    (net (code "49") (name "Net-(74LS32OR-2Y)") (class "Default")
      (node (ref "74LS32OR") (pin "6") (pinfunction "2Y_6") (pintype "unspecified"))
      (node (ref "OR_GATE_EXTRA_3") (pin "3") (pinfunction "3_3") (pintype "input"))
    )
    (net (code "50") (name "Net-(74LS32OR-3A)") (class "Default")
      (node (ref "74LS32OR") (pin "9") (pinfunction "3A_9") (pintype "unspecified"))
      (node (ref "OR_GATE_EXTRA_2") (pin "2") (pinfunction "2_2") (pintype "input"))
    )
    (net (code "51") (name "Net-(74LS32OR-3B)") (class "Default")
      (node (ref "74LS32OR") (pin "10") (pinfunction "3B_10") (pintype "unspecified"))
      (node (ref "OR_GATE_EXTRA_2") (pin "1") (pinfunction "1_1") (pintype "input"))
    )
    (net (code "52") (name "Net-(74LS32OR-3Y)") (class "Default")
      (node (ref "74LS32OR") (pin "8") (pinfunction "3Y_8") (pintype "unspecified"))
      (node (ref "OR_GATE_EXTRA_2") (pin "3") (pinfunction "3_3") (pintype "input"))
    )
    (net (code "53") (name "Net-(74LS32OR-4A)") (class "Default")
      (node (ref "74LS32OR") (pin "12") (pinfunction "4A_12") (pintype "unspecified"))
      (node (ref "OR_GATE_EXTRA_1") (pin "2") (pinfunction "2_2") (pintype "input"))
    )
    (net (code "54") (name "Net-(74LS32OR-4B)") (class "Default")
      (node (ref "74LS32OR") (pin "13") (pinfunction "4B_13") (pintype "unspecified"))
      (node (ref "OR_GATE_EXTRA_1") (pin "1") (pinfunction "1_1") (pintype "input"))
    )
    (net (code "55") (name "Net-(74LS32OR-4Y)") (class "Default")
      (node (ref "74LS32OR") (pin "11") (pinfunction "4Y_11") (pintype "unspecified"))
      (node (ref "OR_GATE_EXTRA_1") (pin "3") (pinfunction "3_3") (pintype "input"))
    )
    (net (code "56") (name "Net-(6502-RDY)") (class "Default")
      (node (ref "6502") (pin "2") (pinfunction "RDY_2") (pintype "unspecified"))
      (node (ref "RDY6502R") (pin "2") (pinfunction "2_2") (pintype "unspecified"))
    )
    (net (code "57") (name "Net-(AT28C256-15PU-CE#)") (class "Default")
      (node (ref "AT28C256-15PU") (pin "20") (pinfunction "CE#_20") (pintype "unspecified"))
      (node (ref "MM74HC1NOR") (pin "12") (pinfunction "A4_12") (pintype "unspecified"))
      (node (ref "MM74HC1NOR") (pin "3") (pinfunction "Y1_3") (pintype "unspecified"))
      (node (ref "MM74HC1NOR") (pin "4") (pinfunction "A2_4") (pintype "unspecified"))
    )
    (net (code "58") (name "Net-(CLOCKSWITCH1-Pad3)") (class "Default")
      (node (ref "CLOCKSWITCH1") (pin "3") (pinfunction "3_3") (pintype "unspecified"))
      (node (ref "OPTIONALCLOCKIN1") (pin "1") (pinfunction "1_1") (pintype "input"))
    )
    (net (code "59") (name "Net-(CLOCK_LED1--)") (class "Default")
      (node (ref "CLOCKLEDR1") (pin "1") (pinfunction "1_1") (pintype "unspecified"))
      (node (ref "CLOCK_LED1") (pin "2") (pinfunction "-_2") (pintype "unspecified"))
    )
    (net (code "60") (name "Net-(MM74HC1NOR-A3)") (class "Default")
      (node (ref "MM74HC1NOR") (pin "9") (pinfunction "A3_9") (pintype "unspecified"))
      (node (ref "NANDGATEEXTRA1") (pin "2") (pinfunction "2_2") (pintype "input"))
    )
    (net (code "61") (name "Net-(MM74HC1NOR-B3)") (class "Default")
      (node (ref "MM74HC1NOR") (pin "10") (pinfunction "B3_10") (pintype "unspecified"))
      (node (ref "NANDGATEEXTRA1") (pin "1") (pinfunction "1_1") (pintype "input"))
    )
    (net (code "62") (name "Net-(MM74HC1NOR-Y3)") (class "Default")
      (node (ref "MM74HC1NOR") (pin "8") (pinfunction "Y3_8") (pintype "unspecified"))
      (node (ref "NANDGATEEXTRA1") (pin "3") (pinfunction "3_3") (pintype "input"))
    )
    (net (code "63") (name "Net-(MM74HC1NOR-Y4)") (class "Default")
      (node (ref "MM74HC1NOR") (pin "11") (pinfunction "Y4_11") (pintype "unspecified"))
      (node (ref "WD65C22") (pin "23") (pinfunction "CS2_23") (pintype "unspecified"))
    )
    (net (code "64") (name "Net-(PA1_OUT_LED-+)") (class "Default")
      (node (ref "PA0_OUT_LED_R31") (pin "2") (pinfunction "2_2") (pintype "unspecified"))
      (node (ref "PA1_OUT_LED") (pin "1") (pinfunction "+_1") (pintype "unspecified"))
    )
    (net (code "65") (name "Net-(POWER_LED1-+)") (class "Default")
      (node (ref "POWER_LED1") (pin "1") (pinfunction "+_1") (pintype "unspecified"))
      (node (ref "POWER_LED_RESISTOR1") (pin "2") (pinfunction "2_2") (pintype "unspecified"))
    )
    (net (code "66") (name "Net-(WD65C22-IRQ)") (class "Default")
      (node (ref "6522_IRQOUT") (pin "1") (pinfunction "1_1") (pintype "input"))
      (node (ref "WD65C22") (pin "21") (pinfunction "IRQ_21") (pintype "unspecified"))
    )
    (net (code "67") (name "clock") (class "Default")
      (node (ref "6502") (pin "37") (pinfunction "PHI2in_37") (pintype "unspecified"))
      (node (ref "CLOCKSWITCH1") (pin "2") (pinfunction "2_2") (pintype "unspecified"))
      (node (ref "CLOCK_LED1") (pin "1") (pinfunction "+_1") (pintype "unspecified"))
      (node (ref "DATAOUT/IN1") (pin "12") (pinfunction "12_12") (pintype "unspecified"))
      (node (ref "MM74HC1NOR") (pin "5") (pinfunction "B2_5") (pintype "unspecified"))
      (node (ref "WD65C22") (pin "25") (pinfunction "PHI2_25") (pintype "unspecified"))
    )
    (net (code "68") (name "diableRam") (class "Default")
      (node (ref "74LS32OR") (pin "2") (pinfunction "1B_2") (pintype "unspecified"))
      (node (ref "DATAOUT/IN1") (pin "9") (pinfunction "9_9") (pintype "unspecified"))
      (node (ref "DIABLERAM_R1") (pin "2") (pinfunction "2_2") (pintype "unspecified"))
    )
    (net (code "69") (name "irq") (class "Default")
      (node (ref "6502") (pin "4") (pinfunction "/IRQ_4") (pintype "unspecified"))
      (node (ref "DATAOUT/IN1") (pin "13") (pinfunction "13_13") (pintype "unspecified"))
      (node (ref "IRQ/NMI_IN2") (pin "2") (pinfunction "2_2") (pintype "input"))
      (node (ref "IRQR1") (pin "2") (pinfunction "2_2") (pintype "unspecified"))
    )
    (net (code "70") (name "nmi") (class "Default")
      (node (ref "6502") (pin "6") (pinfunction "/NMI_6") (pintype "unspecified"))
      (node (ref "DATAOUT/IN1") (pin "14") (pinfunction "14_14") (pintype "unspecified"))
      (node (ref "IRQ/NMI_IN2") (pin "1") (pinfunction "1_1") (pintype "input"))
      (node (ref "NMIR1") (pin "2") (pinfunction "2_2") (pintype "unspecified"))
    )
    (net (code "71") (name "reset") (class "Default")
      (node (ref "6502") (pin "40") (pinfunction "/RES_40") (pintype "unspecified"))
      (node (ref "RESETBUTTON1") (pin "4") (pinfunction "4_4") (pintype "input"))
      (node (ref "RESET_RESISTOR1") (pin "2") (pinfunction "2_2") (pintype "unspecified"))
      (node (ref "WD65C22") (pin "34") (pinfunction "RESET_34") (pintype "unspecified"))
    )
    (net (code "72") (name "r{slash}w") (class "Default")
      (node (ref "6502") (pin "34") (pinfunction "R/W_34") (pintype "unspecified"))
      (node (ref "DATAOUT/IN1") (pin "10") (pinfunction "10_10") (pintype "unspecified"))
      (node (ref "HM62256B") (pin "27") (pinfunction "WE_27") (pintype "unspecified"))
      (node (ref "WD65C22") (pin "22") (pinfunction "R/W_22") (pintype "unspecified"))
    )
    (net (code "73") (name "unconnected-(6502-GND-Pad1)") (class "Default")
      (node (ref "6502") (pin "1") (pinfunction "GND_1") (pintype "unspecified+no_connect"))
    )
    (net (code "74") (name "unconnected-(6502-N.C.-Pad5)") (class "Default")
      (node (ref "6502") (pin "5") (pinfunction "N.C._5") (pintype "unspecified+no_connect"))
    )
    (net (code "75") (name "unconnected-(6502-N.C.-Pad35)") (class "Default")
      (node (ref "6502") (pin "35") (pinfunction "N.C._35") (pintype "unspecified+no_connect"))
    )
    (net (code "76") (name "unconnected-(6502-PHI1out-Pad3)") (class "Default")
      (node (ref "6502") (pin "3") (pinfunction "PHI1out_3") (pintype "unspecified+no_connect"))
    )
    (net (code "77") (name "unconnected-(6502-PHI2out-Pad39)") (class "Default")
      (node (ref "6502") (pin "39") (pinfunction "PHI2out_39") (pintype "unspecified+no_connect"))
    )
    (net (code "78") (name "unconnected-(6502-S.O.-Pad38)") (class "Default")
      (node (ref "6502") (pin "38") (pinfunction "S.O._38") (pintype "unspecified+no_connect"))
    )
    (net (code "79") (name "unconnected-(6502-SYNC-Pad7)") (class "Default")
      (node (ref "6502") (pin "7") (pinfunction "SYNC_7") (pintype "unspecified+no_connect"))
    )
    (net (code "80") (name "unconnected-(LCD1-BLA-Pad15)") (class "Default")
      (node (ref "LCD1") (pin "15") (pinfunction "BLA_15") (pintype "unspecified"))
    )
    (net (code "81") (name "unconnected-(LCD1-BLK-Pad16)") (class "Default")
      (node (ref "LCD1") (pin "16") (pinfunction "BLK_16") (pintype "unspecified"))
    )
    (net (code "82") (name "unconnected-(LCD1-DB0-Pad7)") (class "Default")
      (node (ref "LCD1") (pin "7") (pinfunction "DB0_7") (pintype "unspecified"))
    )
    (net (code "83") (name "unconnected-(LCD1-DB1-Pad8)") (class "Default")
      (node (ref "LCD1") (pin "8") (pinfunction "DB1_8") (pintype "unspecified"))
    )
    (net (code "84") (name "unconnected-(LCD1-DB2-Pad9)") (class "Default")
      (node (ref "LCD1") (pin "9") (pinfunction "DB2_9") (pintype "unspecified"))
    )
    (net (code "85") (name "unconnected-(LCD1-DB3-Pad10)") (class "Default")
      (node (ref "LCD1") (pin "10") (pinfunction "DB3_10") (pintype "unspecified"))
    )
    (net (code "86") (name "unconnected-(LCD1-DB4-Pad11)") (class "Default")
      (node (ref "LCD1") (pin "11") (pinfunction "DB4_11") (pintype "unspecified"))
    )
    (net (code "87") (name "unconnected-(LCD1-DB5-Pad12)") (class "Default")
      (node (ref "LCD1") (pin "12") (pinfunction "DB5_12") (pintype "unspecified"))
    )
    (net (code "88") (name "unconnected-(LCD1-DB6-Pad13)") (class "Default")
      (node (ref "LCD1") (pin "13") (pinfunction "DB6_13") (pintype "unspecified"))
    )
    (net (code "89") (name "unconnected-(LCD1-DB7-Pad14)") (class "Default")
      (node (ref "LCD1") (pin "14") (pinfunction "DB7_14") (pintype "unspecified"))
    )
    (net (code "90") (name "unconnected-(LCD1-E-Pad6)") (class "Default")
      (node (ref "LCD1") (pin "6") (pinfunction "E_6") (pintype "unspecified"))
    )
    (net (code "91") (name "unconnected-(LCD1-RS-Pad4)") (class "Default")
      (node (ref "LCD1") (pin "4") (pinfunction "RS_4") (pintype "unspecified"))
    )
    (net (code "92") (name "unconnected-(LCD1-RW-Pad5)") (class "Default")
      (node (ref "LCD1") (pin "5") (pinfunction "RW_5") (pintype "unspecified"))
    )
    (net (code "93") (name "unconnected-(LCD1-V0-Pad3)") (class "Default")
      (node (ref "LCD1") (pin "3") (pinfunction "V0_3") (pintype "unspecified"))
    )
    (net (code "94") (name "unconnected-(LCD1-VDD-Pad2)") (class "Default")
      (node (ref "LCD1") (pin "2") (pinfunction "VDD_2") (pintype "unspecified"))
    )
    (net (code "95") (name "unconnected-(LCD1-VSS-Pad1)") (class "Default")
      (node (ref "LCD1") (pin "1") (pinfunction "VSS_1") (pintype "unspecified"))
    )
    (net (code "96") (name "unconnected-(MP1-P$1-Pad1)") (class "Default")
      (node (ref "MP1") (pin "1") (pinfunction "P$1_1") (pintype "bidirectional"))
    )
    (net (code "97") (name "unconnected-(MP2-P$1-Pad1)") (class "Default")
      (node (ref "MP2") (pin "1") (pinfunction "P$1_1") (pintype "bidirectional"))
    )
    (net (code "98") (name "unconnected-(MP3-P$1-Pad1)") (class "Default")
      (node (ref "MP3") (pin "1") (pinfunction "P$1_1") (pintype "bidirectional"))
    )
    (net (code "99") (name "unconnected-(MP4-P$1-Pad1)") (class "Default")
      (node (ref "MP4") (pin "1") (pinfunction "P$1_1") (pintype "bidirectional"))
    )
    (net (code "100") (name "unconnected-(MP5-P$1-Pad1)") (class "Default")
      (node (ref "MP5") (pin "1") (pinfunction "P$1_1") (pintype "bidirectional"))
    )
    (net (code "101") (name "unconnected-(MP6-P$1-Pad1)") (class "Default")
      (node (ref "MP6") (pin "1") (pinfunction "P$1_1") (pintype "bidirectional"))
    )
    (net (code "102") (name "unconnected-(MP7-P$1-Pad1)") (class "Default")
      (node (ref "MP7") (pin "1") (pinfunction "P$1_1") (pintype "bidirectional"))
    )
    (net (code "103") (name "unconnected-(MP8-P$1-Pad1)") (class "Default")
      (node (ref "MP8") (pin "1") (pinfunction "P$1_1") (pintype "bidirectional"))
    )
    (net (code "104") (name "unconnected-(POWER_SWITCH1-Pad1)") (class "Default")
      (node (ref "POWER_SWITCH1") (pin "1") (pinfunction "1_1") (pintype "unspecified"))
    )
    (net (code "105") (name "unconnected-(RESETBUTTON1-Pad1)") (class "Default")
      (node (ref "RESETBUTTON1") (pin "1") (pinfunction "1_1") (pintype "input"))
    )
    (net (code "106") (name "unconnected-(RESETBUTTON1-Pad3)") (class "Default")
      (node (ref "RESETBUTTON1") (pin "3") (pinfunction "3_3") (pintype "input"))
    )
    (net (code "107") (name "unconnected-(U1-Pad1)") (class "Default")
      (node (ref "U1") (pin "1") (pinfunction "1_1") (pintype "unspecified"))
    )
    (net (code "108") (name "unconnected-(U1-Pad2)") (class "Default")
      (node (ref "U1") (pin "2") (pinfunction "2_2") (pintype "unspecified"))
    )
    (net (code "109") (name "unconnected-(U1-Pad3)") (class "Default")
      (node (ref "U1") (pin "3") (pinfunction "3_3") (pintype "unspecified"))
    )
    (net (code "110") (name "unconnected-(U1-Pad4)") (class "Default")
      (node (ref "U1") (pin "4") (pinfunction "4_4") (pintype "unspecified"))
    )
    (net (code "111") (name "unconnected-(U1-Pad5)") (class "Default")
      (node (ref "U1") (pin "5") (pinfunction "5_5") (pintype "unspecified"))
    )
    (net (code "112") (name "unconnected-(U1-Pad6)") (class "Default")
      (node (ref "U1") (pin "6") (pinfunction "6_6") (pintype "unspecified"))
    )
    (net (code "113") (name "unconnected-(U1-Pad7)") (class "Default")
      (node (ref "U1") (pin "7") (pinfunction "7_7") (pintype "unspecified"))
    )
    (net (code "114") (name "unconnected-(U1-Pad8)") (class "Default")
      (node (ref "U1") (pin "8") (pinfunction "8_8") (pintype "unspecified"))
    )
    (net (code "115") (name "unconnected-(U1-Pad9)") (class "Default")
      (node (ref "U1") (pin "9") (pinfunction "9_9") (pintype "unspecified"))
    )
    (net (code "116") (name "unconnected-(U1-Pad10)") (class "Default")
      (node (ref "U1") (pin "10") (pinfunction "10_10") (pintype "unspecified"))
    )
    (net (code "117") (name "unconnected-(U1-Pad11)") (class "Default")
      (node (ref "U1") (pin "11") (pinfunction "11_11") (pintype "unspecified"))
    )
    (net (code "118") (name "unconnected-(U1-Pad12)") (class "Default")
      (node (ref "U1") (pin "12") (pinfunction "12_12") (pintype "unspecified"))
    )
    (net (code "119") (name "unconnected-(U1-Pad13)") (class "Default")
      (node (ref "U1") (pin "13") (pinfunction "13_13") (pintype "unspecified"))
    )
    (net (code "120") (name "unconnected-(U1-Pad14)") (class "Default")
      (node (ref "U1") (pin "14") (pinfunction "14_14") (pintype "unspecified"))
    )
    (net (code "121") (name "unconnected-(U1-Pad15)") (class "Default")
      (node (ref "U1") (pin "15") (pinfunction "15_15") (pintype "unspecified"))
    )
    (net (code "122") (name "unconnected-(U1-Pad16)") (class "Default")
      (node (ref "U1") (pin "16") (pinfunction "16_16") (pintype "unspecified"))
    )
    (net (code "123") (name "unconnected-(U1-Pad17)") (class "Default")
      (node (ref "U1") (pin "17") (pinfunction "17_17") (pintype "unspecified"))
    )
    (net (code "124") (name "unconnected-(U1-Pad18)") (class "Default")
      (node (ref "U1") (pin "18") (pinfunction "18_18") (pintype "unspecified"))
    )
    (net (code "125") (name "unconnected-(U1-Pad19)") (class "Default")
      (node (ref "U1") (pin "19") (pinfunction "19_19") (pintype "unspecified"))
    )
    (net (code "126") (name "unconnected-(U1-Pad20)") (class "Default")
      (node (ref "U1") (pin "20") (pinfunction "20_20") (pintype "unspecified"))
    )
    (net (code "127") (name "unconnected-(U1-Pad21)") (class "Default")
      (node (ref "U1") (pin "21") (pinfunction "21_21") (pintype "unspecified"))
    )
    (net (code "128") (name "unconnected-(U1-Pad22)") (class "Default")
      (node (ref "U1") (pin "22") (pinfunction "22_22") (pintype "unspecified"))
    )
    (net (code "129") (name "unconnected-(U1-Pad23)") (class "Default")
      (node (ref "U1") (pin "23") (pinfunction "23_23") (pintype "unspecified"))
    )
    (net (code "130") (name "unconnected-(U1-Pad24)") (class "Default")
      (node (ref "U1") (pin "24") (pinfunction "24_24") (pintype "unspecified"))
    )
    (net (code "131") (name "unconnected-(U1-Pad25)") (class "Default")
      (node (ref "U1") (pin "25") (pinfunction "25_25") (pintype "unspecified"))
    )
    (net (code "132") (name "unconnected-(U1-Pad26)") (class "Default")
      (node (ref "U1") (pin "26") (pinfunction "26_26") (pintype "unspecified"))
    )
    (net (code "133") (name "unconnected-(U1-Pad27)") (class "Default")
      (node (ref "U1") (pin "27") (pinfunction "27_27") (pintype "unspecified"))
    )
    (net (code "134") (name "unconnected-(U1-Pad28)") (class "Default")
      (node (ref "U1") (pin "28") (pinfunction "28_28") (pintype "unspecified"))
    )
    (net (code "135") (name "unconnected-(U1-Pad29)") (class "Default")
      (node (ref "U1") (pin "29") (pinfunction "29_29") (pintype "unspecified"))
    )
    (net (code "136") (name "unconnected-(U1-Pad30)") (class "Default")
      (node (ref "U1") (pin "30") (pinfunction "30_30") (pintype "unspecified"))
    )
    (net (code "137") (name "unconnected-(U1-Pad31)") (class "Default")
      (node (ref "U1") (pin "31") (pinfunction "31_31") (pintype "unspecified"))
    )
    (net (code "138") (name "unconnected-(U1-Pad32)") (class "Default")
      (node (ref "U1") (pin "32") (pinfunction "32_32") (pintype "unspecified"))
    )
    (net (code "139") (name "unconnected-(U1-Pad33)") (class "Default")
      (node (ref "U1") (pin "33") (pinfunction "33_33") (pintype "unspecified"))
    )
    (net (code "140") (name "unconnected-(U1-Pad34)") (class "Default")
      (node (ref "U1") (pin "34") (pinfunction "34_34") (pintype "unspecified"))
    )
    (net (code "141") (name "unconnected-(U1-Pad35)") (class "Default")
      (node (ref "U1") (pin "35") (pinfunction "35_35") (pintype "unspecified"))
    )
    (net (code "142") (name "unconnected-(U1-Pad36)") (class "Default")
      (node (ref "U1") (pin "36") (pinfunction "36_36") (pintype "unspecified"))
    )
    (net (code "143") (name "unconnected-(U1-Pad37)") (class "Default")
      (node (ref "U1") (pin "37") (pinfunction "37_37") (pintype "unspecified"))
    )
    (net (code "144") (name "unconnected-(U1-Pad38)") (class "Default")
      (node (ref "U1") (pin "38") (pinfunction "38_38") (pintype "unspecified"))
    )
    (net (code "145") (name "unconnected-(U1-Pad39)") (class "Default")
      (node (ref "U1") (pin "39") (pinfunction "39_39") (pintype "unspecified"))
    )
    (net (code "146") (name "unconnected-(U1-Pad40)") (class "Default")
      (node (ref "U1") (pin "40") (pinfunction "40_40") (pintype "unspecified"))
    )
    (net (code "147") (name "unconnected-(WD65C22-CA1-Pad40)") (class "Default")
      (node (ref "WD65C22") (pin "40") (pinfunction "CA1_40") (pintype "unspecified+no_connect"))
    )
    (net (code "148") (name "unconnected-(WD65C22-CA2-Pad39)") (class "Default")
      (node (ref "WD65C22") (pin "39") (pinfunction "CA2_39") (pintype "unspecified+no_connect"))
    )
    (net (code "149") (name "unconnected-(WD65C22-CB1-Pad18)") (class "Default")
      (node (ref "WD65C22") (pin "18") (pinfunction "CB1_18") (pintype "unspecified+no_connect"))
    )
    (net (code "150") (name "unconnected-(WD65C22-CB2-Pad19)") (class "Default")
      (node (ref "WD65C22") (pin "19") (pinfunction "CB2_19") (pintype "unspecified+no_connect"))
    )
    (net (code "151") (name "unconnected-(X1-Tri-State-Pad1)") (class "Default")
      (node (ref "X1") (pin "1") (pinfunction "Tri-State_1") (pintype "bidirectional"))
    )
  )
)
